# INA219_CH1.net
KiCad netlist of a schematic drawn in Altium Designer
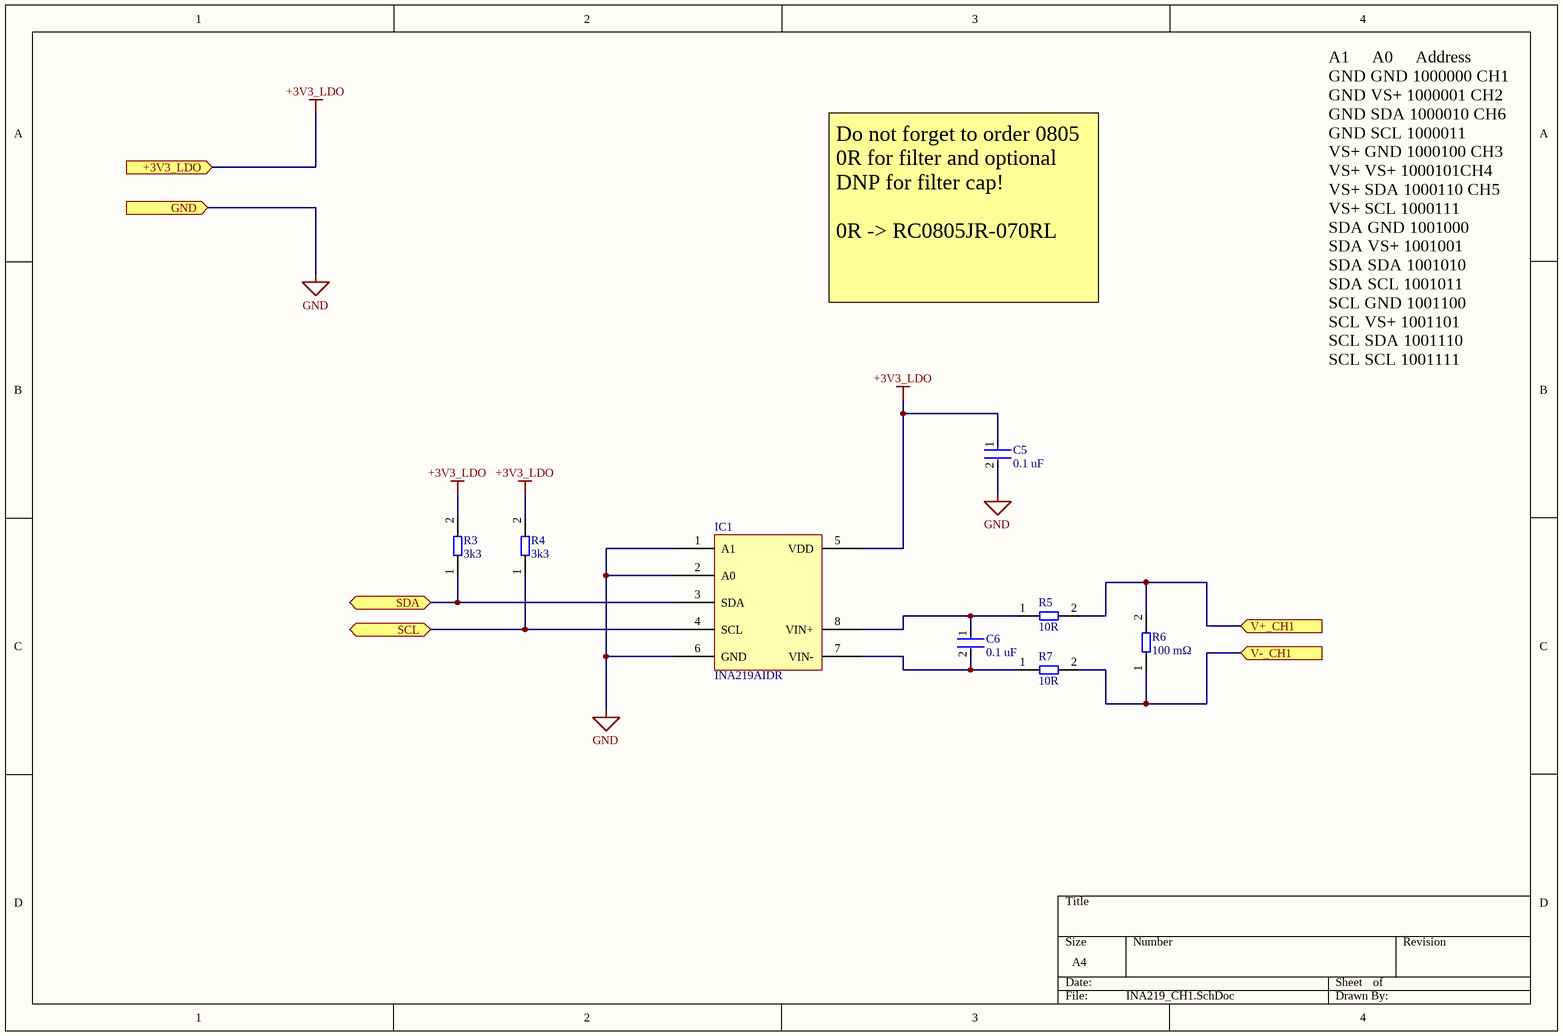
[diagram p0: INA219_CH1.SchDoc]

(export (version "E")
  (design (tool "Eeschema 10.0.6"))
  (components
    (comp (ref "C5")
      (value "0.1 uF")
      (footprint "FP-C0805C-DN-MFG")
      (description "C0805 0.10 μF X7R 30ppm/°C 20.00% 50 V C0805C104M5RAC")
      (fields
        (field (name "MANUFACTURER PART NUMBER") "C0805C104M5RAC")
        (field (name "MANUFACTURER") "KEMET")
      )
      (libsource (lib "Altium Content Vault") (part "b4654b650e69147ec39a6b967a45e02"))
    )
    (comp (ref "C6")
      (value "0.1 uF")
      (footprint "FP-C0805C-DN-MFG")
      (description "C0805 0.10 μF X7R 30ppm/°C 20.00% 50 V C0805C104M5RAC")
      (fields
        (field (name "MANUFACTURER PART NUMBER") "C0805C104M5RAC")
        (field (name "MANUFACTURER") "KEMET")
      )
      (libsource (lib "Altium Content Vault") (part "b4654b650e69147ec39a6b967a45e02"))
    )
    (comp (ref "IC1")
      (value "INA219AIDR")
      (footprint "INA219AIDR")
      (description "Current & Power Monitors & Regulators Zero-Drift,Bi-Dir Crnt/Pwr Monitor")
      (libsource (lib "Callisto Control Board") (part "INA219AIDR"))
    )
    (comp (ref "R3")
      (value "3k3")
      (footprint "0805 Resistor - IPC A")
      (description "Thick Film Resistors - SMD 3.3 kOhms 125 mW 0805 1%\r\nRE0805FRE073K3L")
      (libsource (lib "Callisto Control Board") (part "RE0805FRE073K3L"))
    )
    (comp (ref "R4")
      (value "3k3")
      (footprint "0805 Resistor - IPC A")
      (description "Thick Film Resistors - SMD 3.3 kOhms 125 mW 0805 1%\r\nRE0805FRE073K3L")
      (libsource (lib "Callisto Control Board") (part "RE0805FRE073K3L"))
    )
    (comp (ref "R5")
      (value "10R")
      (footprint "0805 Resistor - IPC A")
      (description "Thick Film Resistors - SMD 10 Ohms 125 mW 0805 1%\r\nRC0805FR-0710RL")
      (libsource (lib "Callisto Control Board") (part "RC0805FR-0710RL"))
    )
    (comp (ref "R6")
      (value "100 mΩ")
      (footprint "PE2512FKM070R1L")
      (description "Current Sense Resistors - SMD 100 mOhms 1 Watt 1 % 75 ppm/C AEC-Q200\r\nPE2512FKM070R1L")
      (libsource (lib "Callisto Control Board") (part "PE2512FKM070R1L"))
    )
    (comp (ref "R7")
      (value "10R")
      (footprint "0805 Resistor - IPC A")
      (description "Thick Film Resistors - SMD 10 Ohms 125 mW 0805 1%\r\nRC0805FR-0710RL")
      (libsource (lib "Callisto Control Board") (part "RC0805FR-0710RL"))
    )
  )
  (nets
    (net (code "1") (name "+3V3_LDO") (class "Default")
      (node (ref "C5") (pin "1") (pinfunction "1_1") (pintype "passive"))
      (node (ref "IC1") (pin "5") (pinfunction "VDD_5") (pintype "passive"))
      (node (ref "R3") (pin "2") (pintype "passive"))
      (node (ref "R4") (pin "2") (pintype "passive"))
    )
    (net (code "2") (name "/SCL") (class "Default")
      (node (ref "IC1") (pin "4") (pinfunction "SCL_4") (pintype "passive"))
      (node (ref "R4") (pin "1") (pintype "passive"))
    )
    (net (code "3") (name "/SDA") (class "Default")
      (node (ref "IC1") (pin "3") (pinfunction "SDA_3") (pintype "passive"))
      (node (ref "R3") (pin "1") (pintype "passive"))
    )
    (net (code "4") (name "/V+_CH1") (class "Default")
      (node (ref "R5") (pin "2") (pintype "passive"))
      (node (ref "R6") (pin "2") (pintype "passive"))
    )
    (net (code "5") (name "/V-_CH1") (class "Default")
      (node (ref "R6") (pin "1") (pintype "passive"))
      (node (ref "R7") (pin "2") (pintype "passive"))
    )
    (net (code "6") (name "GND") (class "Default")
      (node (ref "C5") (pin "2") (pinfunction "2_2") (pintype "passive"))
      (node (ref "IC1") (pin "1") (pinfunction "A1_1") (pintype "passive"))
      (node (ref "IC1") (pin "2") (pinfunction "A0_2") (pintype "passive"))
      (node (ref "IC1") (pin "6") (pinfunction "GND_6") (pintype "passive"))
    )
    (net (code "7") (name "Net-(IC1-VIN+)") (class "Default")
      (node (ref "C6") (pin "1") (pinfunction "1_1") (pintype "passive"))
      (node (ref "IC1") (pin "8") (pinfunction "VIN+_8") (pintype "passive"))
      (node (ref "R5") (pin "1") (pintype "passive"))
    )
    (net (code "8") (name "Net-(IC1-VIN-)") (class "Default")
      (node (ref "C6") (pin "2") (pinfunction "2_2") (pintype "passive"))
      (node (ref "IC1") (pin "7") (pinfunction "VIN-_7") (pintype "passive"))
      (node (ref "R7") (pin "1") (pintype "passive"))
    )
  )
)
